# TopSheet.net
KiCad netlist of a schematic drawn in Altium Designer
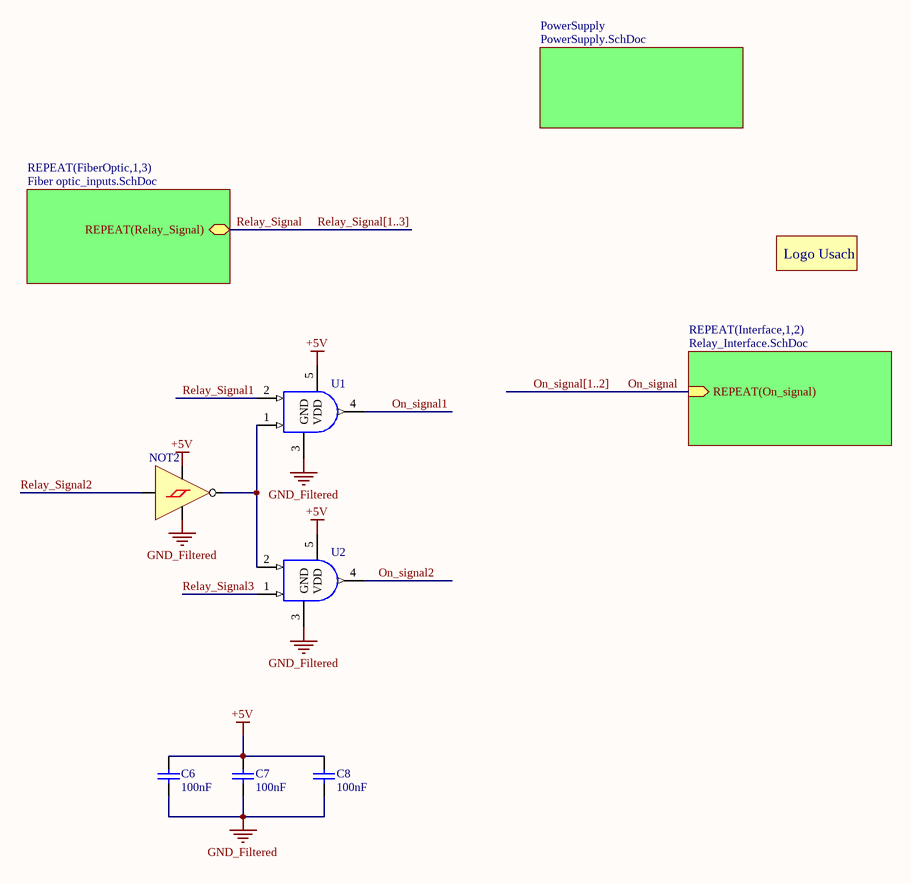
[diagram p0: TopSheet.SchDoc]

(export (version "E")
  (design (tool "Eeschema 10.0.6"))
  (components
    (comp (ref "*")
      (value "LOGO USACH")
      (footprint "Logo Usach")
      (libsource (lib "Componentes_SOC") (part "LOGO USACH"))
    )
    (comp (ref "C6")
      (value "100nF")
      (footprint "Footprints_SOC:CAP_0603")
      (description "Capacitor")
      (fields (field (name "PUBLISHER") "Altium Limited"))
      (libsource (lib "Componentes_SOC") (part "Cap"))
    )
    (comp (ref "C7")
      (value "100nF")
      (footprint "Footprints_SOC:CAP_0603")
      (description "Capacitor")
      (fields (field (name "PUBLISHER") "Altium Limited"))
      (libsource (lib "Componentes_SOC") (part "Cap"))
    )
    (comp (ref "C8")
      (value "100nF")
      (footprint "Footprints_SOC:CAP_0603")
      (description "Capacitor")
      (fields (field (name "PUBLISHER") "Altium Limited"))
      (libsource (lib "Componentes_SOC") (part "Cap"))
    )
    (comp (ref "NOT2")
      (value "INV_CMOS")
      (footprint "INV_SN74AHC1G14DBVR")
      (libsource (lib "Componentes_SOC") (part "INV CMOS"))
    )
    (comp (ref "U1")
      (value "AND Gate")
      (footprint "SOT-23-5")
      (description "2-Input AND Gate")
      (libsource (lib "Componentes_SOC") (part "AND Gate"))
    )
    (comp (ref "U2")
      (value "AND Gate")
      (footprint "SOT-23-5")
      (description "2-Input AND Gate")
      (libsource (lib "Componentes_SOC") (part "AND Gate"))
    )
  )
  (nets
    (net (code "1") (name "+5V") (class "Default")
      (node (ref "C6") (pin "1") (pinfunction "1_1") (pintype "passive"))
      (node (ref "C7") (pin "1") (pinfunction "1_1") (pintype "passive"))
      (node (ref "C8") (pin "1") (pinfunction "1_1") (pintype "passive"))
      (node (ref "NOT2") (pin "5") (pinfunction "Vcc_5") (pintype "passive"))
      (node (ref "U1") (pin "5") (pinfunction "VDD_5") (pintype "power_in"))
      (node (ref "U2") (pin "5") (pinfunction "VDD_5") (pintype "power_in"))
    )
    (net (code "3") (name "/On_signal1") (class "Default")
      (node (ref "U1") (pin "4") (pinfunction "Y_4") (pintype "output"))
    )
    (net (code "4") (name "/On_signal2") (class "Default")
      (node (ref "U2") (pin "4") (pinfunction "Y_4") (pintype "output"))
    )
    (net (code "7") (name "/Relay_Signal1") (class "Default")
      (node (ref "U1") (pin "2") (pinfunction "A_2") (pintype "input"))
    )
    (net (code "8") (name "/Relay_Signal2") (class "Default")
      (node (ref "NOT2") (pin "2") (pinfunction "A_2") (pintype "passive"))
    )
    (net (code "9") (name "/Relay_Signal3") (class "Default")
      (node (ref "U2") (pin "1") (pinfunction "B_1") (pintype "input"))
    )
    (net (code "11") (name "GND_Filtered") (class "Default")
      (node (ref "C6") (pin "2") (pinfunction "2_2") (pintype "passive"))
      (node (ref "C7") (pin "2") (pinfunction "2_2") (pintype "passive"))
      (node (ref "C8") (pin "2") (pinfunction "2_2") (pintype "passive"))
      (node (ref "NOT2") (pin "3") (pinfunction "GND_3") (pintype "passive"))
      (node (ref "U1") (pin "3") (pinfunction "GND_3") (pintype "power_in"))
      (node (ref "U2") (pin "3") (pinfunction "GND_3") (pintype "power_in"))
    )
    (net (code "12") (name "Net-(U1-B)") (class "Default")
      (node (ref "NOT2") (pin "4") (pinfunction "Vcc_4") (pintype "passive"))
      (node (ref "U1") (pin "1") (pinfunction "B_1") (pintype "input"))
      (node (ref "U2") (pin "2") (pinfunction "A_2") (pintype "input"))
    )
    (net (code "13") (name "unconnected-(NOT2-NC-Pad1)") (class "Default")
      (node (ref "NOT2") (pin "1") (pinfunction "NC_1") (pintype "passive"))
    )
  )
)
